# 3EWL1-200001_03.net
KiCad netlist of a schematic drawn in Altium Designer
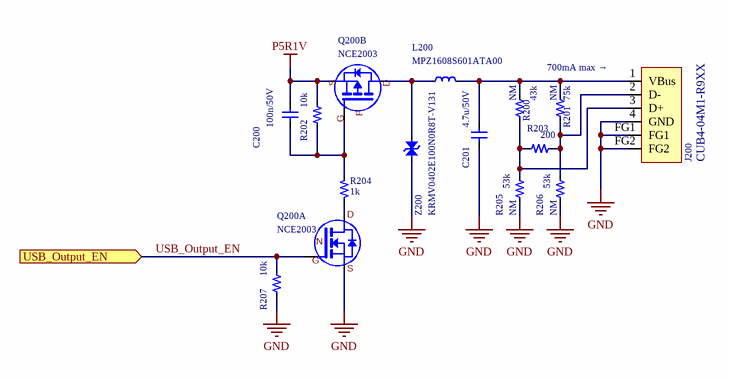
[diagram p0: 3EWL1-200001_03.SchDoc]

(export (version "E")
  (design (tool "Eeschema 10.0.6"))
  (components
    (comp (ref "C200")
      (value "100n/50V")
      (footprint "SC2-1.00X0.50A")
      (description "100n, 50V, X7R, 1005Size")
      (fields
        (field (name "MANUFACTURER") "Walsin")
        (field (name "MANUFACTURER PART NUMBER") "0402B104K500CT")
      )
      (libsource (lib "I_Lib_cronos_NewLayer") (part "C"))
    )
    (comp (ref "C201")
      (value "4.7u/50V")
      (footprint "SC2-3.20X1.60A")
      (description "4.7u/50V, X7R, 3216Size")
      (fields
        (field (name "MANUFACTURER") "Murata")
        (field (name "MANUFACTURER PART NUMBER") "GRM31CR71H475KA12L")
      )
      (libsource (lib "I_Lib_cronos_NewLayer") (part "C"))
    )
    (comp (ref "J200")
      (value "CUB4-04M1-R9XX")
      (footprint "CUB4-04M1-R9XX")
      (description "USB-A")
      (fields (field (name "MANUFACTURER") "Youte Electronic"))
      (libsource (lib "I_Lib_cronos_NewLayer") (part "CUB4-04M1-R9XX"))
    )
    (comp (ref "L200")
      (value "MPZ1608S601ATA00")
      (footprint "SL2-1.60X0.80A")
      (description "600ohm/1.0A/150mohm")
      (fields
        (field (name "MANUFACTURER") "TDK")
        (field (name "MANUFACTURER PART NUMBER") "MPZ1608S601ATA00")
      )
      (libsource (lib "I_Lib_cronos_NewLayer") (part "L"))
    )
    (comp (ref "Q200")
      (value "NCE2003")
      (footprint "SOT23-6")
      (description "N(20V, 55mohm, Vgs(th)=1.2V ), P(-20V, 100mohm, Vgs(th)=-1V), SOT23-6")
      (fields (field (name "MANUFACTURER") "ncepower"))
      (libsource (lib "I_Lib_cronos_NewLayer") (part "NCE2003"))
    )
    (comp (ref "R200")
      (value "43k")
      (footprint "SR2-1.00X0.50A")
      (fields
        (field (name "MANUFACTURER") "YAGEO")
        (field (name "MANUFACTURER PART NUMBER") "RC0402FR-0743KL")
        (field (name "MOUNTING") "NM")
      )
      (libsource (lib "I_Lib_cronos_NewLayer") (part "R"))
    )
    (comp (ref "R201")
      (value "75k")
      (footprint "SR2-1.00X0.50A")
      (fields
        (field (name "MANUFACTURER") "YAGEO")
        (field (name "MANUFACTURER PART NUMBER") "RC0402FR-0775KL")
        (field (name "MOUNTING") "NM")
      )
      (libsource (lib "I_Lib_cronos_NewLayer") (part "R"))
    )
    (comp (ref "R202")
      (value "10k")
      (footprint "SR2-1.00X0.50A")
      (fields
        (field (name "MANUFACTURER") "YAGEO")
        (field (name "MANUFACTURER PART NUMBER") "RC0402FR-0710KL")
      )
      (libsource (lib "I_Lib_cronos_NewLayer") (part "R"))
    )
    (comp (ref "R203")
      (value "200")
      (footprint "SR2-1.00X0.50A")
      (fields
        (field (name "MANUFACTURER") "YAGEO")
        (field (name "MANUFACTURER PART NUMBER") "RC0402FR-07200RL")
      )
      (libsource (lib "I_Lib_cronos_NewLayer") (part "R"))
    )
    (comp (ref "R204")
      (value "1k")
      (footprint "SR2-1.00X0.50A")
      (description "Rsisiter 2pin")
      (fields
        (field (name "MANUFACTURER") "Yageo")
        (field (name "MANUFACTURER PART NUMBER") "RC0402FR-071KL")
      )
      (libsource (lib "I_Lib_cronos") (part "R"))
    )
    (comp (ref "R205")
      (value "53k")
      (footprint "SR2-1.00X0.50A")
      (fields
        (field (name "MANUFACTURER") "YAGEO")
        (field (name "MANUFACTURER PART NUMBER") "RC0402FR-0753KL")
        (field (name "MOUNTING") "NM")
      )
      (libsource (lib "I_Lib_cronos_NewLayer") (part "R"))
    )
    (comp (ref "R206")
      (value "53k")
      (footprint "SR2-1.00X0.50A")
      (fields
        (field (name "MANUFACTURER") "YAGEO")
        (field (name "MANUFACTURER PART NUMBER") "RC0402FR-0753KL")
        (field (name "MOUNTING") "NM")
      )
      (libsource (lib "I_Lib_cronos_NewLayer") (part "R"))
    )
    (comp (ref "R207")
      (value "10k")
      (footprint "SR2-1.00X0.50A")
      (fields
        (field (name "MANUFACTURER") "YAGEO")
        (field (name "MANUFACTURER PART NUMBER") "RC0402FR-0710KL")
      )
      (libsource (lib "I_Lib_cronos_NewLayer") (part "R"))
    )
    (comp (ref "Z200")
      (value "KRMV0402E100N0R8T-V131")
      (footprint "SR2-1.00X0.50A")
      (description "ESD Suppressor")
      (fields
        (field (name "MANUFACTURER") "GRACE")
        (field (name "MANUFACTURER PART NUMBER") "KRMV0402E100N0R8T-V131")
      )
      (libsource (lib "I_Lib_cronos_NewLayer") (part "EZA-EG3A50AV"))
    )
  )
  (nets
    (net (code "1") (name "/USB_Output_EN") (class "Default")
      (node (ref "Q200") (pin "1") (pinfunction "N_G_1") (pintype "passive"))
      (node (ref "R207") (pin "1") (pinfunction "1_1") (pintype "passive"))
    )
    (net (code "2") (name "GND") (class "Default")
      (node (ref "C201") (pin "1") (pinfunction "1_1") (pintype "passive"))
      (node (ref "J200") (pin "4") (pinfunction "GND_4") (pintype "passive"))
      (node (ref "J200") (pin "FG1") (pinfunction "FG1_FG1") (pintype "passive"))
      (node (ref "J200") (pin "FG2") (pinfunction "FG2_FG2") (pintype "passive"))
      (node (ref "Q200") (pin "5") (pinfunction "N_S_5") (pintype "passive"))
      (node (ref "R205") (pin "2") (pinfunction "2_2") (pintype "passive"))
      (node (ref "R206") (pin "2") (pinfunction "2_2") (pintype "passive"))
      (node (ref "R207") (pin "2") (pinfunction "2_2") (pintype "passive"))
      (node (ref "Z200") (pin "1") (pinfunction "1_1") (pintype "passive"))
    )
    (net (code "3") (name "Net-(J200-D+)") (class "Default")
      (node (ref "J200") (pin "3") (pinfunction "D+_3") (pintype "passive"))
      (node (ref "R200") (pin "2") (pinfunction "2_2") (pintype "passive"))
      (node (ref "R203") (pin "1") (pinfunction "1_1") (pintype "passive"))
      (node (ref "R205") (pin "1") (pinfunction "1_1") (pintype "passive"))
    )
    (net (code "4") (name "Net-(J200-D-)") (class "Default")
      (node (ref "J200") (pin "2") (pinfunction "D-_2") (pintype "passive"))
      (node (ref "R201") (pin "2") (pinfunction "2_2") (pintype "passive"))
      (node (ref "R203") (pin "2") (pinfunction "2_2") (pintype "passive"))
      (node (ref "R206") (pin "1") (pinfunction "1_1") (pintype "passive"))
    )
    (net (code "5") (name "Net-(J200-VBus)") (class "Default")
      (node (ref "C201") (pin "2") (pinfunction "2_2") (pintype "passive"))
      (node (ref "J200") (pin "1") (pinfunction "VBus_1") (pintype "passive"))
      (node (ref "L200") (pin "2") (pinfunction "2_2") (pintype "passive"))
      (node (ref "R200") (pin "1") (pinfunction "1_1") (pintype "passive"))
      (node (ref "R201") (pin "1") (pinfunction "1_1") (pintype "passive"))
    )
    (net (code "6") (name "Net-(Q200A-N_D)") (class "Default")
      (node (ref "Q200") (pin "6") (pinfunction "N_D_6") (pintype "passive"))
      (node (ref "R204") (pin "1") (pinfunction "1_1") (pintype "passive"))
    )
    (net (code "7") (name "Net-(Q200B-P_D)") (class "Default")
      (node (ref "L200") (pin "1") (pinfunction "1_1") (pintype "passive"))
      (node (ref "Q200") (pin "4") (pinfunction "P_D_4") (pintype "passive"))
      (node (ref "Z200") (pin "2") (pinfunction "2_2") (pintype "passive"))
    )
    (net (code "8") (name "Net-(Q200B-P_G)") (class "Default")
      (node (ref "C200") (pin "2") (pinfunction "2_2") (pintype "passive"))
      (node (ref "Q200") (pin "3") (pinfunction "P_G_3") (pintype "passive"))
      (node (ref "R202") (pin "2") (pinfunction "2_2") (pintype "passive"))
      (node (ref "R204") (pin "2") (pinfunction "2_2") (pintype "passive"))
    )
    (net (code "9") (name "P5R1V") (class "Default")
      (node (ref "C200") (pin "1") (pinfunction "1_1") (pintype "passive"))
      (node (ref "Q200") (pin "2") (pinfunction "P_S_2") (pintype "passive"))
      (node (ref "R202") (pin "1") (pinfunction "1_1") (pintype "passive"))
    )
  )
)
